# SCH_blinky-project_2025-11-10.net
KiCad netlist of a schematic drawn in EasyEDA
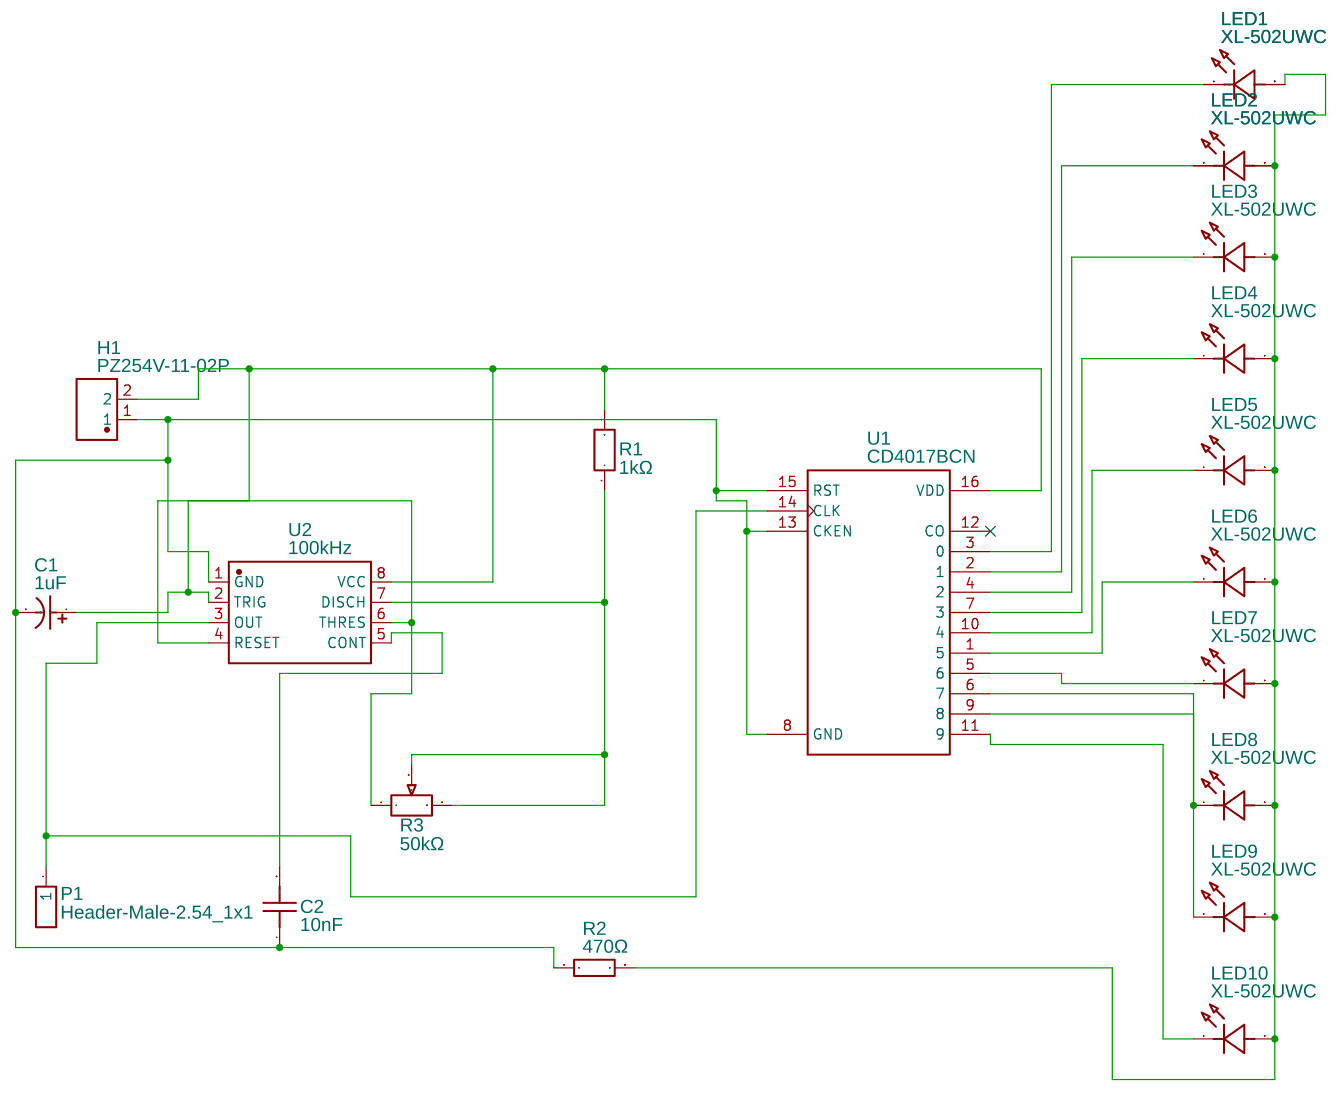
[diagram p0: schematic sheet]

(export (version "E")
  (design (tool "Eeschema 10.0.6"))
  (components
    (comp (ref "C1")
      (value "1uF")
      (fields (field (name "Manufacturer Part") "KF010M050C110A") (field (name "Manufacturer") "CapXon(丰宾)"))
      (libsource (lib "") (part "KF010M050C110A"))
    )
    (comp (ref "C2")
      (value "10nF")
      (fields (field (name "Manufacturer Part") "N09F1B103MN0B0S0N0") (field (name "Manufacturer") "STE(松田)"))
      (libsource (lib "") (part "N09F1B103MN0B0S0N0"))
    )
    (comp (ref "H1")
      (value "PZ254V-11-02P")
      (fields (field (name "Manufacturer") "XFCN(兴飞)"))
      (libsource (lib "") (part "PZ254V-11-02P"))
    )
    (comp (ref "LED1")
      (value "XL-502UWC")
      (fields (field (name "Manufacturer") "XINGLIGHT(成兴光)"))
      (libsource (lib "") (part "XL-502UWC"))
    )
    (comp (ref "LED2")
      (value "XL-502UWC")
      (fields (field (name "Manufacturer") "XINGLIGHT(成兴光)"))
      (libsource (lib "") (part "XL-502UWC"))
    )
    (comp (ref "LED3")
      (value "XL-502UWC")
      (fields (field (name "Manufacturer") "XINGLIGHT(成兴光)"))
      (libsource (lib "") (part "XL-502UWC"))
    )
    (comp (ref "LED4")
      (value "XL-502UWC")
      (fields (field (name "Manufacturer") "XINGLIGHT(成兴光)"))
      (libsource (lib "") (part "XL-502UWC"))
    )
    (comp (ref "LED5")
      (value "XL-502UWC")
      (fields (field (name "Manufacturer") "XINGLIGHT(成兴光)"))
      (libsource (lib "") (part "XL-502UWC"))
    )
    (comp (ref "LED6")
      (value "XL-502UWC")
      (fields (field (name "Manufacturer") "XINGLIGHT(成兴光)"))
      (libsource (lib "") (part "XL-502UWC"))
    )
    (comp (ref "LED7")
      (value "XL-502UWC")
      (fields (field (name "Manufacturer") "XINGLIGHT(成兴光)"))
      (libsource (lib "") (part "XL-502UWC"))
    )
    (comp (ref "LED8")
      (value "XL-502UWC")
      (fields (field (name "Manufacturer") "XINGLIGHT(成兴光)"))
      (libsource (lib "") (part "XL-502UWC"))
    )
    (comp (ref "LED9")
      (value "XL-502UWC")
      (fields (field (name "Manufacturer") "XINGLIGHT(成兴光)"))
      (libsource (lib "") (part "XL-502UWC"))
    )
    (comp (ref "LED10")
      (value "XL-502UWC")
      (fields (field (name "Manufacturer") "XINGLIGHT(成兴光)"))
      (libsource (lib "") (part "XL-502UWC"))
    )
    (comp (ref "P1")
      (value "Header-Male-2.54_1x1")
      (fields (field (name "Manufacturer Part") "2.54-1*1P针") (field (name "Manufacturer") "BOOMELE(博穆精密)"))
      (libsource (lib "") (part "Header-Male-2.54_1x1"))
    )
    (comp (ref "R1")
      (value "1kΩ")
      (fields (field (name "Manufacturer Part") "MF1/4W-1KΩ±1%T52") (field (name "Manufacturer") "华星机电"))
      (libsource (lib "") (part "MF1/4W-1KΩ±1%T52"))
    )
    (comp (ref "R2")
      (value "470Ω")
      (fields
        (field (name "Manufacturer Part") "MFR0W4F4700A50")
        (field (name "Manufacturer") "UNI-ROYAL(厚声)")
      )
      (libsource (lib "") (part "MFR0W4F4700A50"))
    )
    (comp (ref "R3")
      (value "50kΩ")
      (fields (field (name "Manufacturer Part") "3296X-1-503") (field (name "Manufacturer") "BOCHEN(博晨)"))
      (libsource (lib "") (part "3296X-1-503_C118912"))
    )
    (comp (ref "U1") (value "CD4017BCN") (libsource (lib "") (part "CD4017BCN")))
    (comp (ref "U2")
      (value "100kHz")
      (fields (field (name "Manufacturer Part") "NE555P") (field (name "Manufacturer") "TI(德州仪器)"))
      (libsource (lib "") (part "NE555P"))
    )
  )
  (nets
    (net (code "1") (name "Net-(LED1-A)") (class "Default")
      (node (ref "LED1") (pin "2") (pinfunction "A_2") (pintype "unspecified"))
      (node (ref "LED10") (pin "2") (pinfunction "A_2") (pintype "unspecified"))
      (node (ref "LED2") (pin "2") (pinfunction "A_2") (pintype "unspecified"))
      (node (ref "LED3") (pin "2") (pinfunction "A_2") (pintype "unspecified"))
      (node (ref "LED4") (pin "2") (pinfunction "A_2") (pintype "unspecified"))
      (node (ref "LED5") (pin "2") (pinfunction "A_2") (pintype "unspecified"))
      (node (ref "LED6") (pin "2") (pinfunction "A_2") (pintype "unspecified"))
      (node (ref "LED7") (pin "2") (pinfunction "A_2") (pintype "unspecified"))
      (node (ref "LED8") (pin "2") (pinfunction "A_2") (pintype "unspecified"))
      (node (ref "LED9") (pin "2") (pinfunction "A_2") (pintype "unspecified"))
      (node (ref "R2") (pin "2") (pinfunction "2_2") (pintype "input"))
    )
    (net (code "2") (name "Net-(LED1-K)") (class "Default")
      (node (ref "LED1") (pin "1") (pinfunction "K_1") (pintype "unspecified"))
      (node (ref "U1") (pin "3") (pinfunction "0_3") (pintype "output"))
    )
    (net (code "3") (name "Net-(LED2-K)") (class "Default")
      (node (ref "LED2") (pin "1") (pinfunction "K_1") (pintype "unspecified"))
      (node (ref "U1") (pin "2") (pinfunction "1_2") (pintype "output"))
    )
    (net (code "4") (name "Net-(LED3-K)") (class "Default")
      (node (ref "LED3") (pin "1") (pinfunction "K_1") (pintype "unspecified"))
      (node (ref "U1") (pin "4") (pinfunction "2_4") (pintype "output"))
    )
    (net (code "5") (name "Net-(LED4-K)") (class "Default")
      (node (ref "LED4") (pin "1") (pinfunction "K_1") (pintype "unspecified"))
      (node (ref "U1") (pin "7") (pinfunction "3_7") (pintype "output"))
    )
    (net (code "6") (name "Net-(LED5-K)") (class "Default")
      (node (ref "LED5") (pin "1") (pinfunction "K_1") (pintype "unspecified"))
      (node (ref "U1") (pin "10") (pinfunction "4_10") (pintype "output"))
    )
    (net (code "7") (name "Net-(LED6-K)") (class "Default")
      (node (ref "LED6") (pin "1") (pinfunction "K_1") (pintype "unspecified"))
      (node (ref "U1") (pin "1") (pinfunction "5_1") (pintype "output"))
    )
    (net (code "8") (name "Net-(LED7-K)") (class "Default")
      (node (ref "LED7") (pin "1") (pinfunction "K_1") (pintype "unspecified"))
      (node (ref "U1") (pin "5") (pinfunction "6_5") (pintype "output"))
    )
    (net (code "9") (name "Net-(LED8-K)") (class "Default")
      (node (ref "LED8") (pin "1") (pinfunction "K_1") (pintype "unspecified"))
      (node (ref "LED9") (pin "1") (pinfunction "K_1") (pintype "unspecified"))
      (node (ref "U1") (pin "6") (pinfunction "7_6") (pintype "output"))
      (node (ref "U1") (pin "9") (pinfunction "8_9") (pintype "output"))
    )
    (net (code "10") (name "Net-(LED10-K)") (class "Default")
      (node (ref "LED10") (pin "1") (pinfunction "K_1") (pintype "unspecified"))
      (node (ref "U1") (pin "11") (pinfunction "9_11") (pintype "output"))
    )
    (net (code "11") (name "Net-(U1-CKEN)") (class "Default")
      (node (ref "C1") (pin "2") (pinfunction "2_2") (pintype "input"))
      (node (ref "C2") (pin "1") (pinfunction "1_1") (pintype "unspecified"))
      (node (ref "H1") (pin "1") (pinfunction "1_1") (pintype "unspecified"))
      (node (ref "R2") (pin "1") (pinfunction "1_1") (pintype "input"))
      (node (ref "U1") (pin "13") (pinfunction "CKEN_13") (pintype "unspecified"))
      (node (ref "U1") (pin "15") (pinfunction "RST_15") (pintype "unspecified"))
      (node (ref "U1") (pin "8") (pinfunction "GND_8") (pintype "passive"))
      (node (ref "U2") (pin "1") (pinfunction "GND_1") (pintype "unspecified"))
    )
    (net (code "12") (name "Net-(U1-CLK)") (class "Default")
      (node (ref "P1") (pin "1") (pinfunction "1_1") (pintype "input"))
      (node (ref "U1") (pin "14") (pinfunction "CLK_14") (pintype "unspecified"))
      (node (ref "U2") (pin "3") (pinfunction "OUT_3") (pintype "unspecified"))
    )
    (net (code "13") (name "Net-(U1-VDD)") (class "Default")
      (node (ref "H1") (pin "2") (pinfunction "2_2") (pintype "unspecified"))
      (node (ref "R1") (pin "2") (pinfunction "2_2") (pintype "unspecified"))
      (node (ref "U1") (pin "16") (pinfunction "VDD_16") (pintype "passive"))
      (node (ref "U2") (pin "4") (pinfunction "RESET_4") (pintype "unspecified"))
      (node (ref "U2") (pin "8") (pinfunction "VCC_8") (pintype "unspecified"))
    )
    (net (code "14") (name "Net-(U2-CONT)") (class "Default")
      (node (ref "C2") (pin "2") (pinfunction "2_2") (pintype "unspecified"))
      (node (ref "U2") (pin "5") (pinfunction "CONT_5") (pintype "unspecified"))
    )
    (net (code "15") (name "Net-(U2-DISCH)") (class "Default")
      (node (ref "R1") (pin "1") (pinfunction "1_1") (pintype "unspecified"))
      (node (ref "R3") (pin "2") (pinfunction "2_2") (pintype "input"))
      (node (ref "R3") (pin "3") (pinfunction "3_3") (pintype "input"))
      (node (ref "U2") (pin "7") (pinfunction "DISCH_7") (pintype "unspecified"))
    )
    (net (code "16") (name "Net-(U2-THRES)") (class "Default")
      (node (ref "C1") (pin "1") (pinfunction "1_1") (pintype "input"))
      (node (ref "R3") (pin "1") (pinfunction "1_1") (pintype "input"))
      (node (ref "U2") (pin "2") (pinfunction "TRIG_2") (pintype "unspecified"))
      (node (ref "U2") (pin "6") (pinfunction "THRES_6") (pintype "unspecified"))
    )
    (net (code "17") (name "unconnected-(U1-CO-Pad12)") (class "Default")
      (node (ref "U1") (pin "12") (pinfunction "CO_12") (pintype "output+no_connect"))
    )
  )
)
